# SY_HR08_MCU_IO_V1_1.net
KiCad netlist of a schematic drawn in Altium Designer
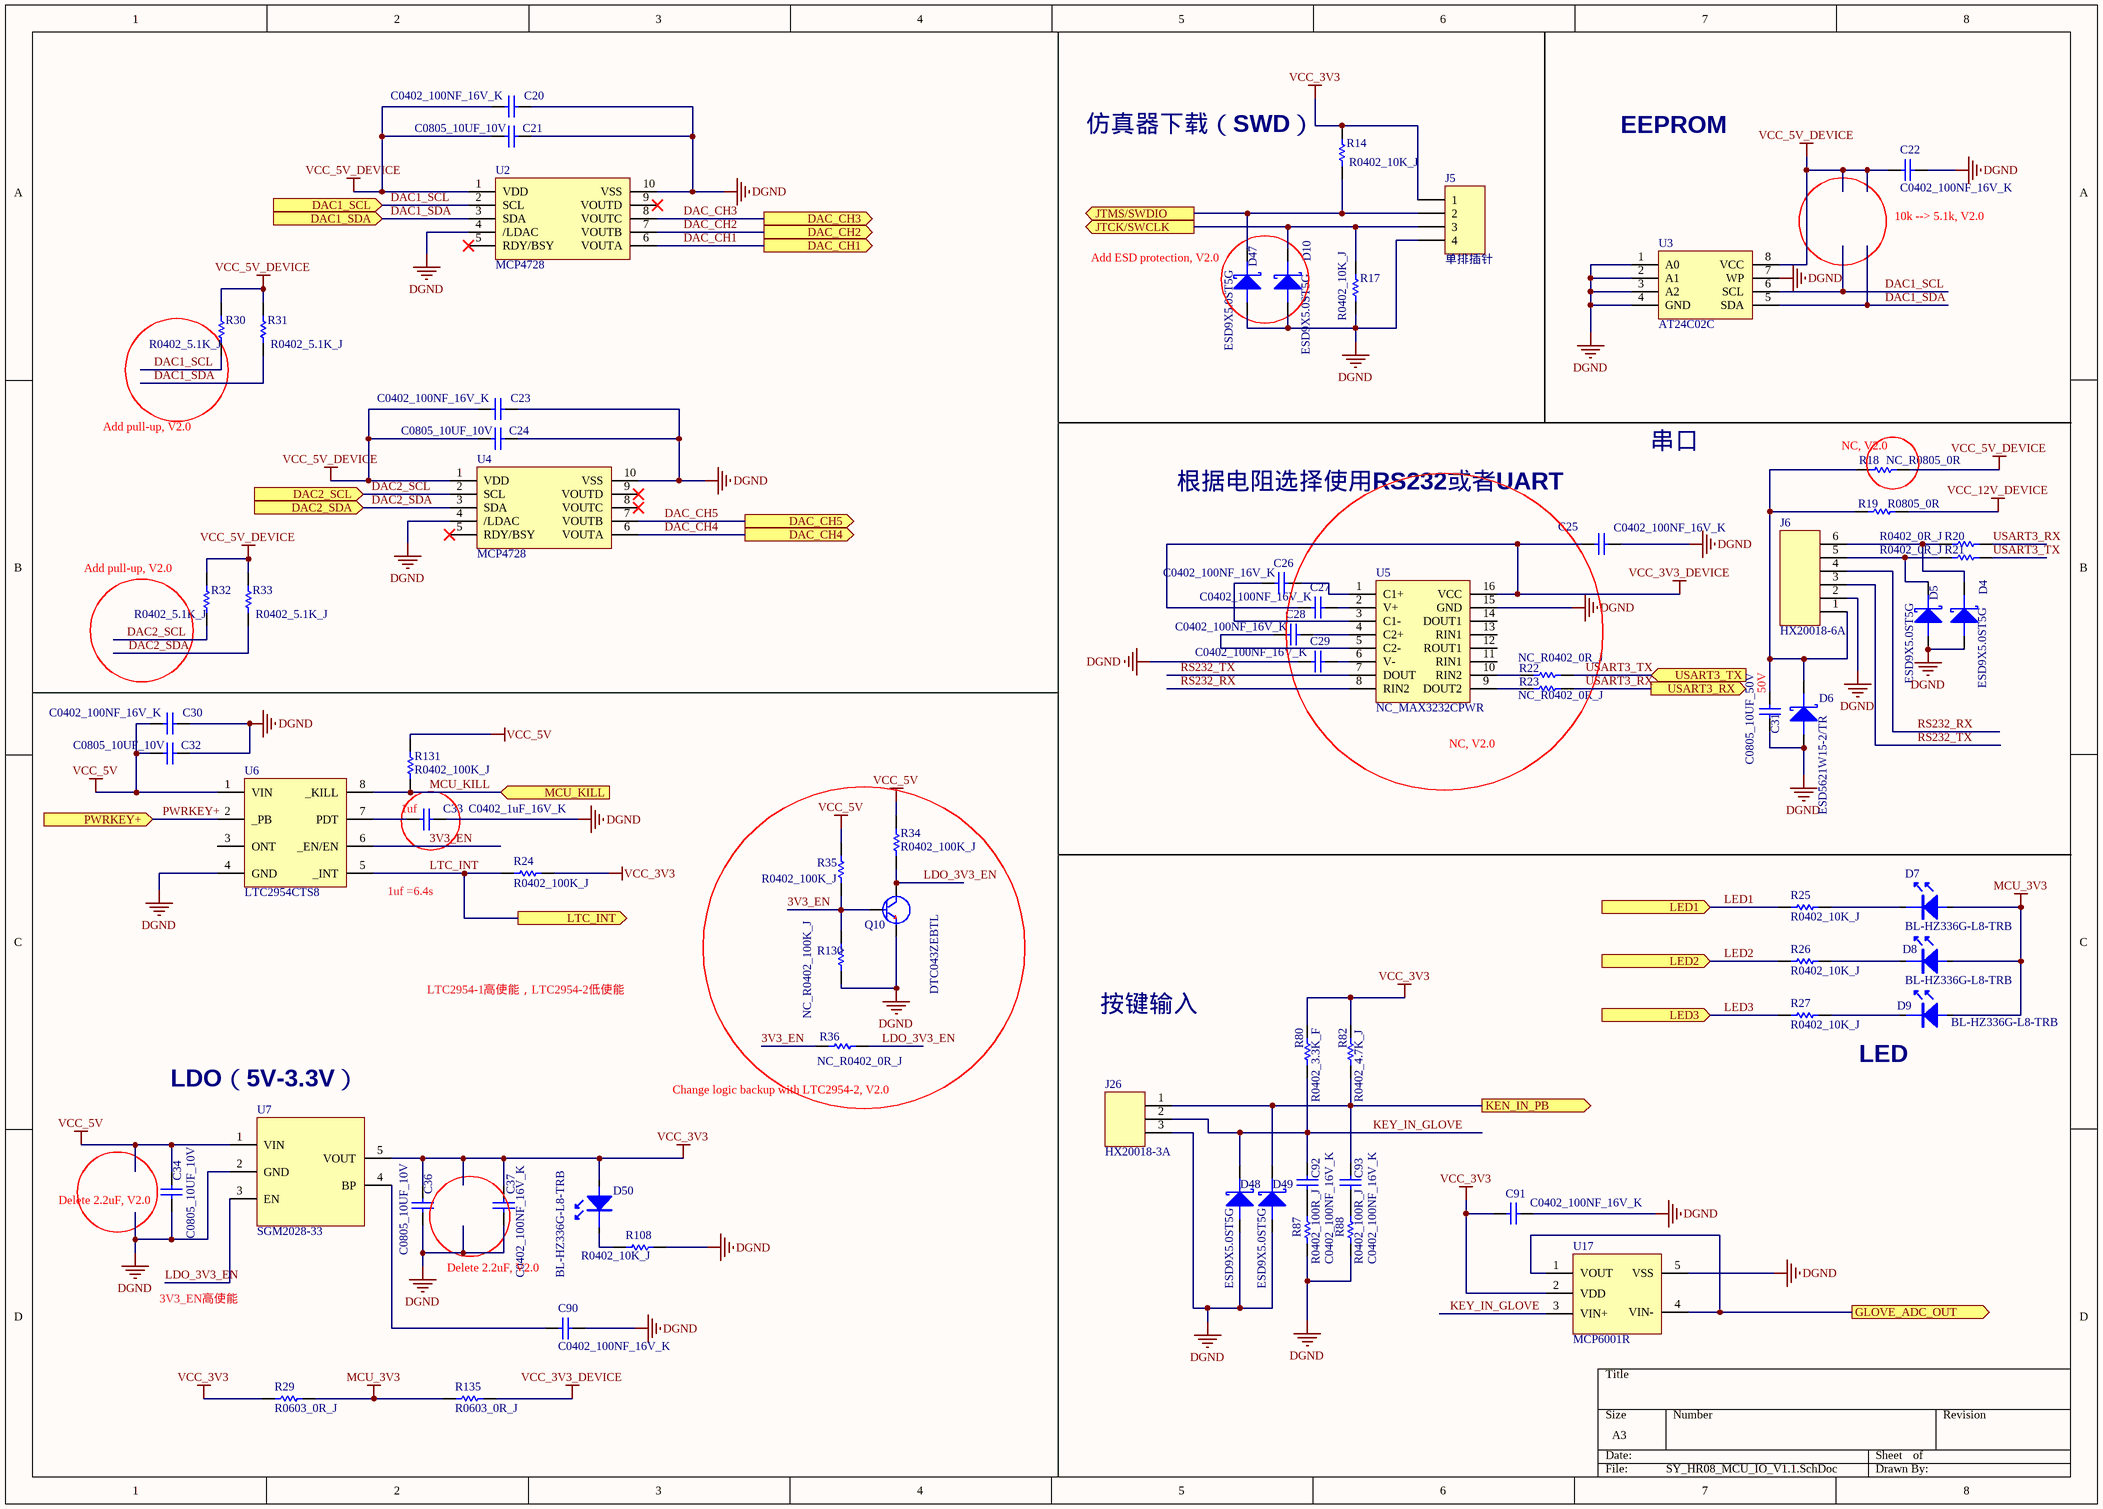
[diagram p0: SY_HR08_MCU_IO_V1.1.SchDoc]

(export (version "E")
  (design (tool "Eeschema 10.0.6"))
  (components
    (comp (ref "C20")
      (value "C0402_100NF_16V_K")
      (footprint "CAP0402_HQ")
      (description "电容_100nF_0402_X7R_16V_K")
      (libsource (lib "zhangky_sch") (part "C0402_100NF_16V_K"))
    )
    (comp (ref "C21")
      (value "C0805_10UF_10V")
      (footprint "CAP0805-B")
      (description "电容_10uF_0805_X5R_10V_K")
      (libsource (lib "zhangky_sch") (part "C0805_10UF_10V"))
    )
    (comp (ref "C22")
      (value "C0402_100NF_16V_K")
      (footprint "CAP0402_HQ")
      (description "电容_100nF_0402_X7R_16V_K")
      (libsource (lib "zhangky_sch") (part "C0402_100NF_16V_K"))
    )
    (comp (ref "C23")
      (value "C0402_100NF_16V_K")
      (footprint "CAP0402_HQ")
      (description "电容_100nF_0402_X7R_16V_K")
      (libsource (lib "zhangky_sch") (part "C0402_100NF_16V_K"))
    )
    (comp (ref "C24")
      (value "C0805_10UF_10V")
      (footprint "CAP0805-B")
      (description "电容_10uF_0805_X5R_10V_K")
      (libsource (lib "zhangky_sch") (part "C0805_10UF_10V"))
    )
    (comp (ref "C25")
      (value "C0402_100NF_16V_K")
      (footprint "CAP0402_HQ")
      (description "电容_100nF_0402_X7R_16V_K")
      (libsource (lib "zhangky_sch") (part "C0402_100NF_16V_K"))
    )
    (comp (ref "C26")
      (value "C0402_100NF_16V_K")
      (footprint "CAP0402_HQ")
      (description "电容_100nF_0402_X7R_16V_K")
      (libsource (lib "zhangky_sch") (part "C0402_100NF_16V_K"))
    )
    (comp (ref "C27")
      (value "C0402_100NF_16V_K")
      (footprint "CAP0402_HQ")
      (description "电容_100nF_0402_X7R_16V_K")
      (libsource (lib "zhangky_sch") (part "C0402_100NF_16V_K"))
    )
    (comp (ref "C28")
      (value "C0402_100NF_16V_K")
      (footprint "CAP0402_HQ")
      (description "电容_100nF_0402_X7R_16V_K")
      (libsource (lib "zhangky_sch") (part "C0402_100NF_16V_K"))
    )
    (comp (ref "C29")
      (value "C0402_100NF_16V_K")
      (footprint "CAP0402_HQ")
      (description "电容_100nF_0402_X7R_16V_K")
      (libsource (lib "zhangky_sch") (part "C0402_100NF_16V_K"))
    )
    (comp (ref "C30")
      (value "C0402_100NF_16V_K")
      (footprint "CAP0402_HQ")
      (description "电容_100nF_0402_X7R_16V_K")
      (libsource (lib "zhangky_sch") (part "C0402_100NF_16V_K"))
    )
    (comp (ref "C31")
      (value "C0805_10UF_50V")
      (footprint "CAP0805-B")
      (description "电容_10uF_0805_X5R_10V_K")
      (libsource (lib "zhangky_sch") (part "C0805_10UF_10V"))
    )
    (comp (ref "C32")
      (value "C0805_10UF_10V")
      (footprint "CAP0805-B")
      (description "电容_10uF_0805_X5R_10V_K")
      (libsource (lib "zhangky_sch") (part "C0805_10UF_10V"))
    )
    (comp (ref "C33")
      (value "C0402_1uF_16V_K")
      (footprint "CAP0402_HQ")
      (description "电容_100nF_0402_X7R_16V_K")
      (libsource (lib "zhangky_sch") (part "C0402_100NF_16V_K"))
    )
    (comp (ref "C34")
      (value "C0805_10UF_10V")
      (footprint "CAP0805-B")
      (description "电容_10uF_0805_X5R_10V_K")
      (libsource (lib "zhangky_sch") (part "C0805_10UF_10V"))
    )
    (comp (ref "C36")
      (value "C0805_10UF_10V")
      (footprint "CAP0805-B")
      (description "电容_10uF_0805_X5R_10V_K")
      (libsource (lib "zhangky_sch") (part "C0805_10UF_10V"))
    )
    (comp (ref "C37")
      (value "C0402_100NF_16V_K")
      (footprint "CAP0402_HQ")
      (description "电容_100nF_0402_X7R_16V_K")
      (libsource (lib "zhangky_sch") (part "C0402_100NF_16V_K"))
    )
    (comp (ref "C90")
      (value "C0402_100NF_16V_K")
      (footprint "CAP0402_HQ")
      (description "电容_100nF_0402_X7R_16V_K")
      (libsource (lib "zhangky_sch") (part "C0402_100NF_16V_K"))
    )
    (comp (ref "C91")
      (value "C0402_100NF_16V_K")
      (footprint "CAP0402_HQ")
      (description "电容_100nF_0402_X7R_16V_K")
      (libsource (lib "zhangky_sch") (part "C0402_100NF_16V_K"))
    )
    (comp (ref "C92")
      (value "C0402_100NF_16V_K")
      (footprint "CAP0402_HQ")
      (description "电容_100nF_0402_X7R_16V_K")
      (libsource (lib "zhangky_sch") (part "C0402_100NF_16V_K"))
    )
    (comp (ref "C93")
      (value "C0402_100NF_16V_K")
      (footprint "CAP0402_HQ")
      (description "电容_100nF_0402_X7R_16V_K")
      (libsource (lib "zhangky_sch") (part "C0402_100NF_16V_K"))
    )
    (comp (ref "D4")
      (value "ESD9X5.0ST5G")
      (footprint "ESD9X5.0ST5G")
      (description "TVS_单路_单向_5.0V_65pF")
      (fields (field (name "MANUFACTURER") "ONSEMI(安森美)") (field (name "PART NUMBER") "HQ11510010010"))
      (libsource (lib "zhangky_sch") (part "ESD9X5.0ST5G"))
    )
    (comp (ref "D5")
      (value "ESD9X5.0ST5G")
      (footprint "ESD9X5.0ST5G")
      (description "TVS_单路_单向_5.0V_65pF")
      (fields (field (name "MANUFACTURER") "ONSEMI(安森美)") (field (name "PART NUMBER") "HQ11510010010"))
      (libsource (lib "zhangky_sch") (part "ESD9X5.0ST5G"))
    )
    (comp (ref "D6")
      (value "ESD5621W15-2/TR")
      (footprint "ESD5621W15-SOD323F")
      (description "TVS_浪涌+静电二合一管_单向_15V_270pf")
      (libsource (lib "zhangky_sch") (part "ESD5621W15-2/TR"))
    )
    (comp (ref "D7")
      (value "BL-HZ336G-L8-TRB")
      (footprint "LED_1.6_0.8_0.4")
      (description "LED_(白色_0603_2.8V)_(HUE仅收5-5,5-6,5-7的标示，CAE仅收含P的标示)")
      (fields (field (name "MANUFACTURER") "Bright(佰鸿)"))
      (libsource (lib "zhangky_sch") (part "BL-HZ336G-L8-TRB"))
    )
    (comp (ref "D8")
      (value "BL-HZ336G-L8-TRB")
      (footprint "LED_1.6_0.8_0.4")
      (description "LED_(白色_0603_2.8V)_(HUE仅收5-5,5-6,5-7的标示，CAE仅收含P的标示)")
      (fields (field (name "MANUFACTURER") "Bright(佰鸿)"))
      (libsource (lib "zhangky_sch") (part "BL-HZ336G-L8-TRB"))
    )
    (comp (ref "D9")
      (value "BL-HZ336G-L8-TRB")
      (footprint "LED_1.6_0.8_0.4")
      (description "LED_(白色_0603_2.8V)_(HUE仅收5-5,5-6,5-7的标示，CAE仅收含P的标示)")
      (fields (field (name "MANUFACTURER") "Bright(佰鸿)"))
      (libsource (lib "zhangky_sch") (part "BL-HZ336G-L8-TRB"))
    )
    (comp (ref "D10")
      (value "ESD9X5.0ST5G")
      (footprint "ESD9X5.0ST5G")
      (description "TVS_单路_单向_5.0V_65pF")
      (fields (field (name "MANUFACTURER") "ONSEMI(安森美)") (field (name "PART NUMBER") "HQ11510010010"))
      (libsource (lib "zhangky_sch") (part "ESD9X5.0ST5G"))
    )
    (comp (ref "D47")
      (value "ESD9X5.0ST5G")
      (footprint "ESD9X5.0ST5G")
      (description "TVS_单路_单向_5.0V_65pF")
      (fields (field (name "MANUFACTURER") "ONSEMI(安森美)") (field (name "PART NUMBER") "HQ11510010010"))
      (libsource (lib "zhangky_sch") (part "ESD9X5.0ST5G"))
    )
    (comp (ref "D48")
      (value "ESD9X5.0ST5G")
      (footprint "ESD9X5.0ST5G")
      (description "TVS_单路_单向_5.0V_65pF")
      (fields (field (name "MANUFACTURER") "ONSEMI(安森美)") (field (name "PART NUMBER") "HQ11510010010"))
      (libsource (lib "zhangky_sch") (part "ESD9X5.0ST5G"))
    )
    (comp (ref "D49")
      (value "ESD9X5.0ST5G")
      (footprint "ESD9X5.0ST5G")
      (description "TVS_单路_单向_5.0V_65pF")
      (fields (field (name "MANUFACTURER") "ONSEMI(安森美)") (field (name "PART NUMBER") "HQ11510010010"))
      (libsource (lib "zhangky_sch") (part "ESD9X5.0ST5G"))
    )
    (comp (ref "D50")
      (value "BL-HZ336G-L8-TRB")
      (footprint "LED_1.6_0.8_0.4")
      (description "LED_(白色_0603_2.8V)_(HUE仅收5-5,5-6,5-7的标示，CAE仅收含P的标示)")
      (fields (field (name "MANUFACTURER") "Bright(佰鸿)"))
      (libsource (lib "zhangky_sch") (part "BL-HZ336G-L8-TRB"))
    )
    (comp (ref "J5")
      (value "单排插针")
      (footprint "CON1X4(2.54mm)")
      (description "Header, 4-Pin")
      (fields (field (name "PUBLISHER") "Altium Limited"))
      (libsource (lib "YS-F1Pro开发板主板") (part "Header 4"))
    )
    (comp (ref "J6")
      (value "HX20018-6A")
      (footprint "HX20018-6A")
      (description "HX20018-6A  2.0mm")
      (libsource (lib "zhangky_sch") (part "HX20018-6A"))
    )
    (comp (ref "J26")
      (value "HX20018-3A")
      (footprint "HX20018-3A")
      (description "HX20018-3A  2.0mm")
      (libsource (lib "zhangky_sch") (part "HX20018-3A"))
    )
    (comp (ref "Q10")
      (value "DTC043ZEBTL")
      (footprint "DTC043ZEBTL$2F$$2F$DTC143ZE$2F$$2F$LDTC143ZET1G")
      (description "NPN三极管_100mA_EMT3F")
      (libsource (lib "zhangky_sch") (part "DTC043ZEBTL"))
    )
    (comp (ref "R14")
      (value "R0402_10K_J")
      (footprint "RES0402_HQ")
      (description "电阻10K(0402-0.0625W-J)")
      (libsource (lib "zhangky_sch") (part "R0402_10K_J"))
    )
    (comp (ref "R17")
      (value "R0402_10K_J")
      (footprint "RES0402_HQ")
      (description "电阻10K(0402-0.0625W-J)")
      (libsource (lib "zhangky_sch") (part "R0402_10K_J"))
    )
    (comp (ref "R18")
      (value "NC_R0805_0R")
      (footprint "RES0805")
      (description "电阻0R(0805-0.125W-J)")
      (libsource (lib "zhangky_sch") (part "R0805_0R"))
    )
    (comp (ref "R19")
      (value "R0805_0R")
      (footprint "RES0805")
      (description "电阻0R(0805-0.125W-J)")
      (libsource (lib "zhangky_sch") (part "R0805_0R"))
    )
    (comp (ref "R20")
      (value "R0402_0R_J")
      (footprint "RES0402_HQ")
      (description "电阻0R(0402-0.0625W-J)")
      (libsource (lib "zhangky_sch") (part "R0402_0R_J"))
    )
    (comp (ref "R21")
      (value "R0402_0R_J")
      (footprint "RES0402_HQ")
      (description "电阻0R(0402-0.0625W-J)")
      (libsource (lib "zhangky_sch") (part "R0402_0R_J"))
    )
    (comp (ref "R22")
      (value "NC_R0402_0R_J")
      (footprint "RES0402_HQ")
      (description "电阻0R(0402-0.0625W-J)")
      (libsource (lib "zhangky_sch") (part "R0402_0R_J"))
    )
    (comp (ref "R23")
      (value "NC_R0402_0R_J")
      (footprint "RES0402_HQ")
      (description "电阻0R(0402-0.0625W-J)")
      (libsource (lib "zhangky_sch") (part "R0402_0R_J"))
    )
    (comp (ref "R24")
      (value "R0402_100K_J")
      (footprint "RES0402_HQ")
      (description "电阻10K(0402-0.0625W-J)")
      (libsource (lib "zhangky_sch") (part "R0402_10K_J"))
    )
    (comp (ref "R25")
      (value "R0402_10K_J")
      (footprint "RES0402_HQ-A")
      (description "电阻_1K(0402-0.0625W-J)")
      (libsource (lib "zhangky_sch") (part "R0402_1K_1/16W_J"))
    )
    (comp (ref "R26")
      (value "R0402_10K_J")
      (footprint "RES0402_HQ-A")
      (description "电阻_1K(0402-0.0625W-J)")
      (libsource (lib "zhangky_sch") (part "R0402_1K_1/16W_J"))
    )
    (comp (ref "R27")
      (value "R0402_10K_J")
      (footprint "RES0402_HQ-A")
      (description "电阻_1K(0402-0.0625W-J)")
      (libsource (lib "zhangky_sch") (part "R0402_1K_1/16W_J"))
    )
    (comp (ref "R29")
      (value "R0603_0R_J")
      (footprint "RES0603-A")
      (description "电阻0R(0603-0.1W-J)")
      (libsource (lib "zhangky_sch") (part "R0603_0R_J"))
    )
    (comp (ref "R30")
      (value "R0402_5.1K_J")
      (footprint "RES0402_HQ")
      (description "电阻10K(0402-0.0625W-J)")
      (libsource (lib "zhangky_sch") (part "R0402_10K_J"))
    )
    (comp (ref "R31")
      (value "R0402_5.1K_J")
      (footprint "RES0402_HQ")
      (description "电阻10K(0402-0.0625W-J)")
      (libsource (lib "zhangky_sch") (part "R0402_10K_J"))
    )
    (comp (ref "R32")
      (value "R0402_5.1K_J")
      (footprint "RES0402_HQ")
      (description "电阻10K(0402-0.0625W-J)")
      (libsource (lib "zhangky_sch") (part "R0402_10K_J"))
    )
    (comp (ref "R33")
      (value "R0402_5.1K_J")
      (footprint "RES0402_HQ")
      (description "电阻10K(0402-0.0625W-J)")
      (libsource (lib "zhangky_sch") (part "R0402_10K_J"))
    )
    (comp (ref "R34")
      (value "R0402_100K_J")
      (footprint "RES0402_HQ")
      (description "电阻10K(0402-0.0625W-J)")
      (libsource (lib "zhangky_sch") (part "R0402_10K_J"))
    )
    (comp (ref "R35")
      (value "R0402_100K_J")
      (footprint "RES0402_HQ")
      (description "电阻10K(0402-0.0625W-J)")
      (libsource (lib "zhangky_sch") (part "R0402_10K_J"))
    )
    (comp (ref "R36")
      (value "NC_R0402_0R_J")
      (footprint "RES0402_HQ")
      (description "电阻10K(0402-0.0625W-J)")
      (libsource (lib "zhangky_sch") (part "R0402_10K_J"))
    )
    (comp (ref "R80")
      (value "R0402_3.3K_F")
      (footprint "RES0402_HQ")
      (description "电阻4.7K(0402-0.0625W-J)")
      (libsource (lib "zhangky_sch") (part "R0402_4.7K_J"))
    )
    (comp (ref "R82")
      (value "R0402_4.7K_J")
      (footprint "RES0402_HQ")
      (description "电阻4.7K(0402-0.0625W-J)")
      (libsource (lib "zhangky_sch") (part "R0402_4.7K_J"))
    )
    (comp (ref "R87")
      (value "R0402_100R_J")
      (footprint "RES0402_HQ")
      (description "电阻100R(0402-0.0625W-J)")
      (libsource (lib "zhangky_sch") (part "R0402_100R_J"))
    )
    (comp (ref "R88")
      (value "R0402_100R_J")
      (footprint "RES0402_HQ")
      (description "电阻100R(0402-0.0625W-J)")
      (libsource (lib "zhangky_sch") (part "R0402_100R_J"))
    )
    (comp (ref "R108")
      (value "R0402_10K_J")
      (footprint "RES0402_HQ-A")
      (description "电阻_1K(0402-0.0625W-J)")
      (libsource (lib "zhangky_sch") (part "R0402_1K_1/16W_J"))
    )
    (comp (ref "R130")
      (value "NC_R0402_100K_J")
      (footprint "RES0402_HQ")
      (description "电阻10K(0402-0.0625W-J)")
      (libsource (lib "zhangky_sch") (part "R0402_10K_J"))
    )
    (comp (ref "R131")
      (value "R0402_100K_J")
      (footprint "RES0402_HQ")
      (description "电阻10K(0402-0.0625W-J)")
      (libsource (lib "zhangky_sch") (part "R0402_10K_J"))
    )
    (comp (ref "R135")
      (value "R0603_0R_J")
      (footprint "RES0603-A")
      (description "电阻0R(0603-0.1W-J)")
      (libsource (lib "zhangky_sch") (part "R0603_0R_J"))
    )
    (comp (ref "U2")
      (value "MCP4728")
      (footprint "MSOP-10 - 2")
      (description "MCP4728  4路DAC  I2C   MSOP10")
      (libsource (lib "zhangky_sch") (part "MCP4728"))
    )
    (comp (ref "U3")
      (value "AT24C02C")
      (footprint "SOIC8_39MM")
      (description "2K位串行CMOS E2PROM I2C接口")
      (libsource (lib "zhangky_sch") (part "AT24C02C"))
    )
    (comp (ref "U4")
      (value "MCP4728")
      (footprint "MSOP-10 - 2")
      (description "MCP4728  4路DAC  I2C   MSOP10")
      (libsource (lib "zhangky_sch") (part "MCP4728"))
    )
    (comp (ref "U5")
      (value "NC_MAX3232CPWR")
      (footprint "MAX3232CPWR")
      (description "UART转RS232 芯片")
      (fields (field (name "MANUFACTURER") "TI"))
      (libsource (lib "zhangky_sch") (part "MAX3232CPWR"))
    )
    (comp (ref "U6")
      (value "LTC2954CTS8")
      (footprint "LTC2954CTS8")
      (description "Pushbutton On/Off")
      (libsource (lib "zhangky_sch") (part "LTC2954CTS8"))
    )
    (comp (ref "U7")
      (value "SGM2028-33")
      (footprint "TPS7B6950")
      (description "单电池电压转换器  3.3V")
      (libsource (lib "zhangky_sch") (part "RT9193-33"))
    )
    (comp (ref "U17")
      (value "MCP6001R")
      (footprint "TOS23")
      (description "1MHz, Low-Power Op Amp")
      (libsource (lib "zhangky_sch") (part "MCP6001R"))
    )
  )
  (nets
    (net (code "1") (name "/3V3_EN") (class "Default")
      (node (ref "Q10") (pin "1") (pinfunction "B_1") (pintype "passive"))
      (node (ref "R130") (pin "2") (pinfunction "2_2") (pintype "passive"))
      (node (ref "R35") (pin "1") (pinfunction "1_1") (pintype "passive"))
      (node (ref "R36") (pin "1") (pinfunction "1_1") (pintype "passive"))
      (node (ref "U6") (pin "6") (pinfunction "_EN/EN_6") (pintype "passive"))
    )
    (net (code "2") (name "/DAC1_SCL") (class "Default")
      (node (ref "R30") (pin "1") (pinfunction "1_1") (pintype "passive"))
      (node (ref "U2") (pin "2") (pinfunction "SCL_2") (pintype "passive"))
      (node (ref "U3") (pin "6") (pinfunction "SCL_6") (pintype "passive"))
    )
    (net (code "3") (name "/DAC1_SDA") (class "Default")
      (node (ref "R31") (pin "1") (pinfunction "1_1") (pintype "passive"))
      (node (ref "U2") (pin "3") (pinfunction "SDA_3") (pintype "passive"))
      (node (ref "U3") (pin "5") (pinfunction "SDA_5") (pintype "passive"))
    )
    (net (code "4") (name "/DAC2_SCL") (class "Default")
      (node (ref "R32") (pin "1") (pinfunction "1_1") (pintype "passive"))
      (node (ref "U4") (pin "2") (pinfunction "SCL_2") (pintype "passive"))
    )
    (net (code "5") (name "/DAC2_SDA") (class "Default")
      (node (ref "R33") (pin "1") (pinfunction "1_1") (pintype "passive"))
      (node (ref "U4") (pin "3") (pinfunction "SDA_3") (pintype "passive"))
    )
    (net (code "6") (name "/DAC_CH1") (class "Default")
      (node (ref "U2") (pin "6") (pinfunction "VOUTA_6") (pintype "passive"))
    )
    (net (code "7") (name "/DAC_CH2") (class "Default")
      (node (ref "U2") (pin "7") (pinfunction "VOUTB_7") (pintype "passive"))
    )
    (net (code "8") (name "/DAC_CH3") (class "Default")
      (node (ref "U2") (pin "8") (pinfunction "VOUTC_8") (pintype "passive"))
    )
    (net (code "9") (name "/DAC_CH4") (class "Default")
      (node (ref "U4") (pin "6") (pinfunction "VOUTA_6") (pintype "passive"))
    )
    (net (code "10") (name "/DAC_CH5") (class "Default")
      (node (ref "U4") (pin "7") (pinfunction "VOUTB_7") (pintype "passive"))
    )
    (net (code "11") (name "/GLOVE_ADC_OUT") (class "Default")
      (node (ref "U17") (pin "1") (pinfunction "VOUT_1") (pintype "passive"))
      (node (ref "U17") (pin "4") (pinfunction "VIN-_4") (pintype "passive"))
    )
    (net (code "12") (name "/JTCK{slash}SWCLK") (class "Default")
      (node (ref "D10") (pin "1") (pinfunction "1_1") (pintype "passive"))
      (node (ref "J5") (pin "3") (pinfunction "3_3") (pintype "passive"))
      (node (ref "R17") (pin "2") (pinfunction "2_2") (pintype "passive"))
    )
    (net (code "13") (name "/JTMS{slash}SWDIO") (class "Default")
      (node (ref "D47") (pin "1") (pinfunction "1_1") (pintype "passive"))
      (node (ref "J5") (pin "2") (pinfunction "2_2") (pintype "passive"))
      (node (ref "R14") (pin "1") (pinfunction "1_1") (pintype "passive"))
    )
    (net (code "14") (name "/KEN_IN_PB") (class "Default")
      (node (ref "C93") (pin "2") (pinfunction "2_2") (pintype "passive"))
      (node (ref "D49") (pin "1") (pinfunction "1_1") (pintype "passive"))
      (node (ref "J26") (pin "1") (pinfunction "1_1") (pintype "passive"))
      (node (ref "R82") (pin "2") (pinfunction "2_2") (pintype "passive"))
    )
    (net (code "15") (name "/KEY_IN_GLOVE") (class "Default")
      (node (ref "C92") (pin "2") (pinfunction "2_2") (pintype "passive"))
      (node (ref "D48") (pin "1") (pinfunction "1_1") (pintype "passive"))
      (node (ref "J26") (pin "2") (pinfunction "2_2") (pintype "passive"))
      (node (ref "R80") (pin "2") (pinfunction "2_2") (pintype "passive"))
      (node (ref "U17") (pin "3") (pinfunction "VIN+_3") (pintype "passive"))
    )
    (net (code "16") (name "/LDO_3V3_EN") (class "Default")
      (node (ref "Q10") (pin "3") (pinfunction "C_3") (pintype "passive"))
      (node (ref "R34") (pin "1") (pinfunction "1_1") (pintype "passive"))
      (node (ref "R36") (pin "2") (pinfunction "2_2") (pintype "passive"))
      (node (ref "U7") (pin "3") (pinfunction "EN_3") (pintype "passive"))
    )
    (net (code "17") (name "/LED1") (class "Default")
      (node (ref "R25") (pin "1") (pinfunction "1_1") (pintype "passive"))
    )
    (net (code "18") (name "/LED2") (class "Default")
      (node (ref "R26") (pin "1") (pinfunction "1_1") (pintype "passive"))
    )
    (net (code "19") (name "/LED3") (class "Default")
      (node (ref "R27") (pin "1") (pinfunction "1_1") (pintype "passive"))
    )
    (net (code "20") (name "/LTC_INT") (class "Default")
      (node (ref "R24") (pin "1") (pinfunction "1_1") (pintype "passive"))
      (node (ref "U6") (pin "5") (pinfunction "_INT_5") (pintype "passive"))
    )
    (net (code "21") (name "/MCU_KILL") (class "Default")
      (node (ref "R131") (pin "1") (pinfunction "1_1") (pintype "passive"))
      (node (ref "U6") (pin "8") (pinfunction "_KILL_8") (pintype "passive"))
    )
    (net (code "22") (name "/PWRKEY+") (class "Default")
      (node (ref "U6") (pin "2") (pinfunction "_PB_2") (pintype "passive"))
    )
    (net (code "23") (name "/RS232_RX") (class "Default")
      (node (ref "J6") (pin "4") (pinfunction "4_4") (pintype "passive"))
      (node (ref "U5") (pin "8") (pinfunction "RIN2_8") (pintype "passive"))
    )
    (net (code "24") (name "/RS232_TX") (class "Default")
      (node (ref "J6") (pin "3") (pinfunction "3_3") (pintype "passive"))
      (node (ref "U5") (pin "7") (pinfunction "DOUT_7") (pintype "passive"))
    )
    (net (code "25") (name "/USART3_RX") (class "Default")
      (node (ref "R20") (pin "2") (pinfunction "2_2") (pintype "passive"))
      (node (ref "R23") (pin "2") (pinfunction "2_2") (pintype "passive"))
    )
    (net (code "26") (name "/USART3_TX") (class "Default")
      (node (ref "R21") (pin "2") (pinfunction "2_2") (pintype "passive"))
      (node (ref "R22") (pin "2") (pinfunction "2_2") (pintype "passive"))
    )
    (net (code "27") (name "DGND") (class "Default")
      (node (ref "C20") (pin "2") (pinfunction "2_2") (pintype "passive"))
      (node (ref "C21") (pin "1") (pinfunction "1_1") (pintype "passive"))
      (node (ref "C22") (pin "1") (pinfunction "1_1") (pintype "passive"))
      (node (ref "C23") (pin "2") (pinfunction "2_2") (pintype "passive"))
      (node (ref "C24") (pin "1") (pinfunction "1_1") (pintype "passive"))
      (node (ref "C25") (pin "2") (pinfunction "2_2") (pintype "passive"))
      (node (ref "C29") (pin "1") (pinfunction "1_1") (pintype "passive"))
      (node (ref "C30") (pin "2") (pinfunction "2_2") (pintype "passive"))
      (node (ref "C31") (pin "1") (pinfunction "1_1") (pintype "passive"))
      (node (ref "C32") (pin "1") (pinfunction "1_1") (pintype "passive"))
      (node (ref "C33") (pin "2") (pinfunction "2_2") (pintype "passive"))
      (node (ref "C34") (pin "1") (pinfunction "1_1") (pintype "passive"))
      (node (ref "C36") (pin "1") (pinfunction "1_1") (pintype "passive"))
      (node (ref "C37") (pin "1") (pinfunction "1_1") (pintype "passive"))
      (node (ref "C90") (pin "1") (pinfunction "1_1") (pintype "passive"))
      (node (ref "C91") (pin "2") (pinfunction "2_2") (pintype "passive"))
      (node (ref "D10") (pin "2") (pinfunction "2_2") (pintype "passive"))
      (node (ref "D4") (pin "2") (pinfunction "2_2") (pintype "passive"))
      (node (ref "D47") (pin "2") (pinfunction "2_2") (pintype "passive"))
      (node (ref "D48") (pin "2") (pinfunction "2_2") (pintype "passive"))
      (node (ref "D49") (pin "2") (pinfunction "2_2") (pintype "passive"))
      (node (ref "D5") (pin "2") (pinfunction "2_2") (pintype "passive"))
      (node (ref "D6") (pin "2") (pinfunction "2_2") (pintype "passive"))
      (node (ref "J26") (pin "3") (pinfunction "3_3") (pintype "passive"))
      (node (ref "J5") (pin "4") (pinfunction "4_4") (pintype "passive"))
      (node (ref "J6") (pin "2") (pinfunction "2_2") (pintype "passive"))
      (node (ref "Q10") (pin "2") (pinfunction "E_2") (pintype "passive"))
      (node (ref "R108") (pin "2") (pinfunction "2_2") (pintype "passive"))
      (node (ref "R130") (pin "1") (pinfunction "1_1") (pintype "passive"))
      (node (ref "R17") (pin "1") (pinfunction "1_1") (pintype "passive"))
      (node (ref "R87") (pin "1") (pinfunction "1_1") (pintype "passive"))
      (node (ref "R88") (pin "1") (pinfunction "1_1") (pintype "passive"))
      (node (ref "U17") (pin "5") (pinfunction "VSS_5") (pintype "passive"))
      (node (ref "U2") (pin "10") (pinfunction "VSS_10") (pintype "passive"))
      (node (ref "U2") (pin "4") (pinfunction "/LDAC_4") (pintype "passive"))
      (node (ref "U3") (pin "1") (pinfunction "A0_1") (pintype "passive"))
      (node (ref "U3") (pin "2") (pinfunction "A1_2") (pintype "passive"))
      (node (ref "U3") (pin "3") (pinfunction "A2_3") (pintype "passive"))
      (node (ref "U3") (pin "4") (pinfunction "GND_4") (pintype "passive"))
      (node (ref "U3") (pin "7") (pinfunction "WP_7") (pintype "passive"))
      (node (ref "U4") (pin "10") (pinfunction "VSS_10") (pintype "passive"))
      (node (ref "U4") (pin "4") (pinfunction "/LDAC_4") (pintype "passive"))
      (node (ref "U5") (pin "15") (pinfunction "GND_15") (pintype "passive"))
      (node (ref "U6") (pin "4") (pinfunction "GND_4") (pintype "passive"))
      (node (ref "U7") (pin "2") (pinfunction "GND_2") (pintype "passive"))
    )
    (net (code "28") (name "MCU_3V3") (class "Default")
      (node (ref "D7") (pin "2") (pinfunction "2_2") (pintype "passive"))
      (node (ref "D8") (pin "2") (pinfunction "2_2") (pintype "passive"))
      (node (ref "D9") (pin "2") (pinfunction "2_2") (pintype "passive"))
      (node (ref "R135") (pin "1") (pinfunction "1_1") (pintype "passive"))
      (node (ref "R29") (pin "2") (pinfunction "2_2") (pintype "passive"))
    )
    (net (code "29") (name "Net-(C31-Pad2)") (class "Default")
      (node (ref "C31") (pin "2") (pinfunction "2_2") (pintype "passive"))
      (node (ref "D6") (pin "1") (pinfunction "1_1") (pintype "passive"))
      (node (ref "J6") (pin "1") (pinfunction "1_1") (pintype "passive"))
      (node (ref "R18") (pin "1") (pinfunction "1_1") (pintype "passive"))
      (node (ref "R19") (pin "1") (pinfunction "1_1") (pintype "passive"))
    )
    (net (code "30") (name "Net-(C92-Pad1)") (class "Default")
      (node (ref "C92") (pin "1") (pinfunction "1_1") (pintype "passive"))
      (node (ref "R87") (pin "2") (pinfunction "2_2") (pintype "passive"))
    )
    (net (code "31") (name "Net-(C93-Pad1)") (class "Default")
      (node (ref "C93") (pin "1") (pinfunction "1_1") (pintype "passive"))
      (node (ref "R88") (pin "2") (pinfunction "2_2") (pintype "passive"))
    )
    (net (code "32") (name "Net-(D4-Pad1)") (class "Default")
      (node (ref "D4") (pin "1") (pinfunction "1_1") (pintype "passive"))
      (node (ref "J6") (pin "6") (pinfunction "6_6") (pintype "passive"))
      (node (ref "R20") (pin "1") (pinfunction "1_1") (pintype "passive"))
    )
    (net (code "33") (name "Net-(D5-Pad1)") (class "Default")
      (node (ref "D5") (pin "1") (pinfunction "1_1") (pintype "passive"))
      (node (ref "J6") (pin "5") (pinfunction "5_5") (pintype "passive"))
      (node (ref "R21") (pin "1") (pinfunction "1_1") (pintype "passive"))
    )
    (net (code "34") (name "Net-(D7-Pad1)") (class "Default")
      (node (ref "D7") (pin "1") (pinfunction "1_1") (pintype "passive"))
      (node (ref "R25") (pin "2") (pinfunction "2_2") (pintype "passive"))
    )
    (net (code "35") (name "Net-(D8-Pad1)") (class "Default")
      (node (ref "D8") (pin "1") (pinfunction "1_1") (pintype "passive"))
      (node (ref "R26") (pin "2") (pinfunction "2_2") (pintype "passive"))
    )
    (net (code "36") (name "Net-(D9-Pad1)") (class "Default")
      (node (ref "D9") (pin "1") (pinfunction "1_1") (pintype "passive"))
      (node (ref "R27") (pin "2") (pinfunction "2_2") (pintype "passive"))
    )
    (net (code "37") (name "Net-(D50-Pad1)") (class "Default")
      (node (ref "D50") (pin "1") (pinfunction "1_1") (pintype "passive"))
      (node (ref "R108") (pin "1") (pinfunction "1_1") (pintype "passive"))
    )
    (net (code "38") (name "Net-(R22-Pad1)") (class "Default")
      (node (ref "R22") (pin "1") (pinfunction "1_1") (pintype "passive"))
      (node (ref "U5") (pin "10") (pinfunction "RIN2_10") (pintype "passive"))
    )
    (net (code "39") (name "Net-(U5-C1+)") (class "Default")
      (node (ref "C26") (pin "2") (pinfunction "2_2") (pintype "passive"))
      (node (ref "U5") (pin "1") (pinfunction "C1+_1") (pintype "passive"))
    )
    (net (code "40") (name "Net-(U5-C1-)") (class "Default")
      (node (ref "C26") (pin "1") (pinfunction "1_1") (pintype "passive"))
      (node (ref "U5") (pin "3") (pinfunction "C1-_3") (pintype "passive"))
    )
    (net (code "41") (name "Net-(U5-C2+)") (class "Default")
      (node (ref "C28") (pin "2") (pinfunction "2_2") (pintype "passive"))
      (node (ref "U5") (pin "4") (pinfunction "C2+_4") (pintype "passive"))
    )
    (net (code "42") (name "Net-(U5-C2-)") (class "Default")
      (node (ref "C28") (pin "1") (pinfunction "1_1") (pintype "passive"))
      (node (ref "U5") (pin "5") (pinfunction "C2-_5") (pintype "passive"))
    )
    (net (code "43") (name "Net-(U5-DOUT2)") (class "Default")
      (node (ref "R23") (pin "1") (pinfunction "1_1") (pintype "passive"))
      (node (ref "U5") (pin "9") (pinfunction "DOUT2_9") (pintype "passive"))
    )
    (net (code "44") (name "Net-(U5-V+)") (class "Default")
      (node (ref "C27") (pin "2") (pinfunction "2_2") (pintype "passive"))
      (node (ref "U5") (pin "2") (pinfunction "V+_2") (pintype "passive"))
    )
    (net (code "45") (name "Net-(U5-V-)") (class "Default")
      (node (ref "C29") (pin "2") (pinfunction "2_2") (pintype "passive"))
      (node (ref "U5") (pin "6") (pinfunction "V-_6") (pintype "passive"))
    )
    (net (code "46") (name "Net-(U6-PDT)") (class "Default")
      (node (ref "C33") (pin "1") (pinfunction "1_1") (pintype "passive"))
      (node (ref "U6") (pin "7") (pinfunction "PDT_7") (pintype "passive"))
    )
    (net (code "47") (name "Net-(U7-BP)") (class "Default")
      (node (ref "C90") (pin "2") (pinfunction "2_2") (pintype "passive"))
      (node (ref "U7") (pin "4") (pinfunction "BP_4") (pintype "passive"))
    )
    (net (code "48") (name "VCC_3V3") (class "Default")
      (node (ref "C36") (pin "2") (pinfunction "2_2") (pintype "passive"))
      (node (ref "C37") (pin "2") (pinfunction "2_2") (pintype "passive"))
      (node (ref "C91") (pin "1") (pinfunction "1_1") (pintype "passive"))
      (node (ref "D50") (pin "2") (pinfunction "2_2") (pintype "passive"))
      (node (ref "J5") (pin "1") (pinfunction "1_1") (pintype "passive"))
      (node (ref "R14") (pin "2") (pinfunction "2_2") (pintype "passive"))
      (node (ref "R24") (pin "2") (pinfunction "2_2") (pintype "passive"))
      (node (ref "R29") (pin "1") (pinfunction "1_1") (pintype "passive"))
      (node (ref "R80") (pin "1") (pinfunction "1_1") (pintype "passive"))
      (node (ref "R82") (pin "1") (pinfunction "1_1") (pintype "passive"))
      (node (ref "U17") (pin "2") (pinfunction "VDD_2") (pintype "passive"))
      (node (ref "U7") (pin "5") (pinfunction "VOUT_5") (pintype "passive"))
    )
    (net (code "49") (name "VCC_3V3_DEVICE") (class "Default")
      (node (ref "C25") (pin "1") (pinfunction "1_1") (pintype "passive"))
      (node (ref "C27") (pin "1") (pinfunction "1_1") (pintype "passive"))
      (node (ref "R135") (pin "2") (pinfunction "2_2") (pintype "passive"))
      (node (ref "U5") (pin "16") (pinfunction "VCC_16") (pintype "passive"))
    )
    (net (code "50") (name "VCC_5V") (class "Default")
      (node (ref "C30") (pin "1") (pinfunction "1_1") (pintype "passive"))
      (node (ref "C32") (pin "2") (pinfunction "2_2") (pintype "passive"))
      (node (ref "C34") (pin "2") (pinfunction "2_2") (pintype "passive"))
      (node (ref "R131") (pin "2") (pinfunction "2_2") (pintype "passive"))
      (node (ref "R34") (pin "2") (pinfunction "2_2") (pintype "passive"))
      (node (ref "R35") (pin "2") (pinfunction "2_2") (pintype "passive"))
      (node (ref "U6") (pin "1") (pinfunction "VIN_1") (pintype "passive"))
      (node (ref "U7") (pin "1") (pinfunction "VIN_1") (pintype "passive"))
    )
    (net (code "51") (name "VCC_5V_DEVICE") (class "Default")
      (node (ref "C20") (pin "1") (pinfunction "1_1") (pintype "passive"))
      (node (ref "C21") (pin "2") (pinfunction "2_2") (pintype "passive"))
      (node (ref "C22") (pin "2") (pinfunction "2_2") (pintype "passive"))
      (node (ref "C23") (pin "1") (pinfunction "1_1") (pintype "passive"))
      (node (ref "C24") (pin "2") (pinfunction "2_2") (pintype "passive"))
      (node (ref "R18") (pin "2") (pinfunction "2_2") (pintype "passive"))
      (node (ref "R30") (pin "2") (pinfunction "2_2") (pintype "passive"))
      (node (ref "R31") (pin "2") (pinfunction "2_2") (pintype "passive"))
      (node (ref "R32") (pin "2") (pinfunction "2_2") (pintype "passive"))
      (node (ref "R33") (pin "2") (pinfunction "2_2") (pintype "passive"))
      (node (ref "U2") (pin "1") (pinfunction "VDD_1") (pintype "passive"))
      (node (ref "U3") (pin "8") (pinfunction "VCC_8") (pintype "passive"))
      (node (ref "U4") (pin "1") (pinfunction "VDD_1") (pintype "passive"))
    )
    (net (code "52") (name "VCC_12V_DEVICE") (class "Default")
      (node (ref "R19") (pin "2") (pinfunction "2_2") (pintype "passive"))
    )
    (net (code "53") (name "unconnected-(U2-RDY{slash}BSY-Pad5)") (class "Default")
      (node (ref "U2") (pin "5") (pinfunction "RDY/BSY_5") (pintype "passive+no_connect"))
    )
    (net (code "54") (name "unconnected-(U2-VOUTD-Pad9)") (class "Default")
      (node (ref "U2") (pin "9") (pinfunction "VOUTD_9") (pintype "passive+no_connect"))
    )
    (net (code "55") (name "unconnected-(U4-RDY{slash}BSY-Pad5)") (class "Default")
      (node (ref "U4") (pin "5") (pinfunction "RDY/BSY_5") (pintype "passive+no_connect"))
    )
    (net (code "56") (name "unconnected-(U4-VOUTC-Pad8)") (class "Default")
      (node (ref "U4") (pin "8") (pinfunction "VOUTC_8") (pintype "passive+no_connect"))
    )
    (net (code "57") (name "unconnected-(U4-VOUTD-Pad9)") (class "Default")
      (node (ref "U4") (pin "9") (pinfunction "VOUTD_9") (pintype "passive+no_connect"))
    )
    (net (code "58") (name "unconnected-(U5-DOUT1-Pad14)") (class "Default")
      (node (ref "U5") (pin "14") (pinfunction "DOUT1_14") (pintype "passive"))
    )
    (net (code "59") (name "unconnected-(U5-RIN1-Pad11)") (class "Default")
      (node (ref "U5") (pin "11") (pinfunction "RIN1_11") (pintype "passive"))
    )
    (net (code "60") (name "unconnected-(U5-RIN1-Pad13)") (class "Default")
      (node (ref "U5") (pin "13") (pinfunction "RIN1_13") (pintype "passive"))
    )
    (net (code "61") (name "unconnected-(U5-ROUT1-Pad12)") (class "Default")
      (node (ref "U5") (pin "12") (pinfunction "ROUT1_12") (pintype "passive"))
    )
    (net (code "62") (name "unconnected-(U6-ONT-Pad3)") (class "Default")
      (node (ref "U6") (pin "3") (pinfunction "ONT_3") (pintype "passive"))
    )
  )
)
